# KIT_UNAZ.net
KiCad netlist of a schematic drawn in EAGLE
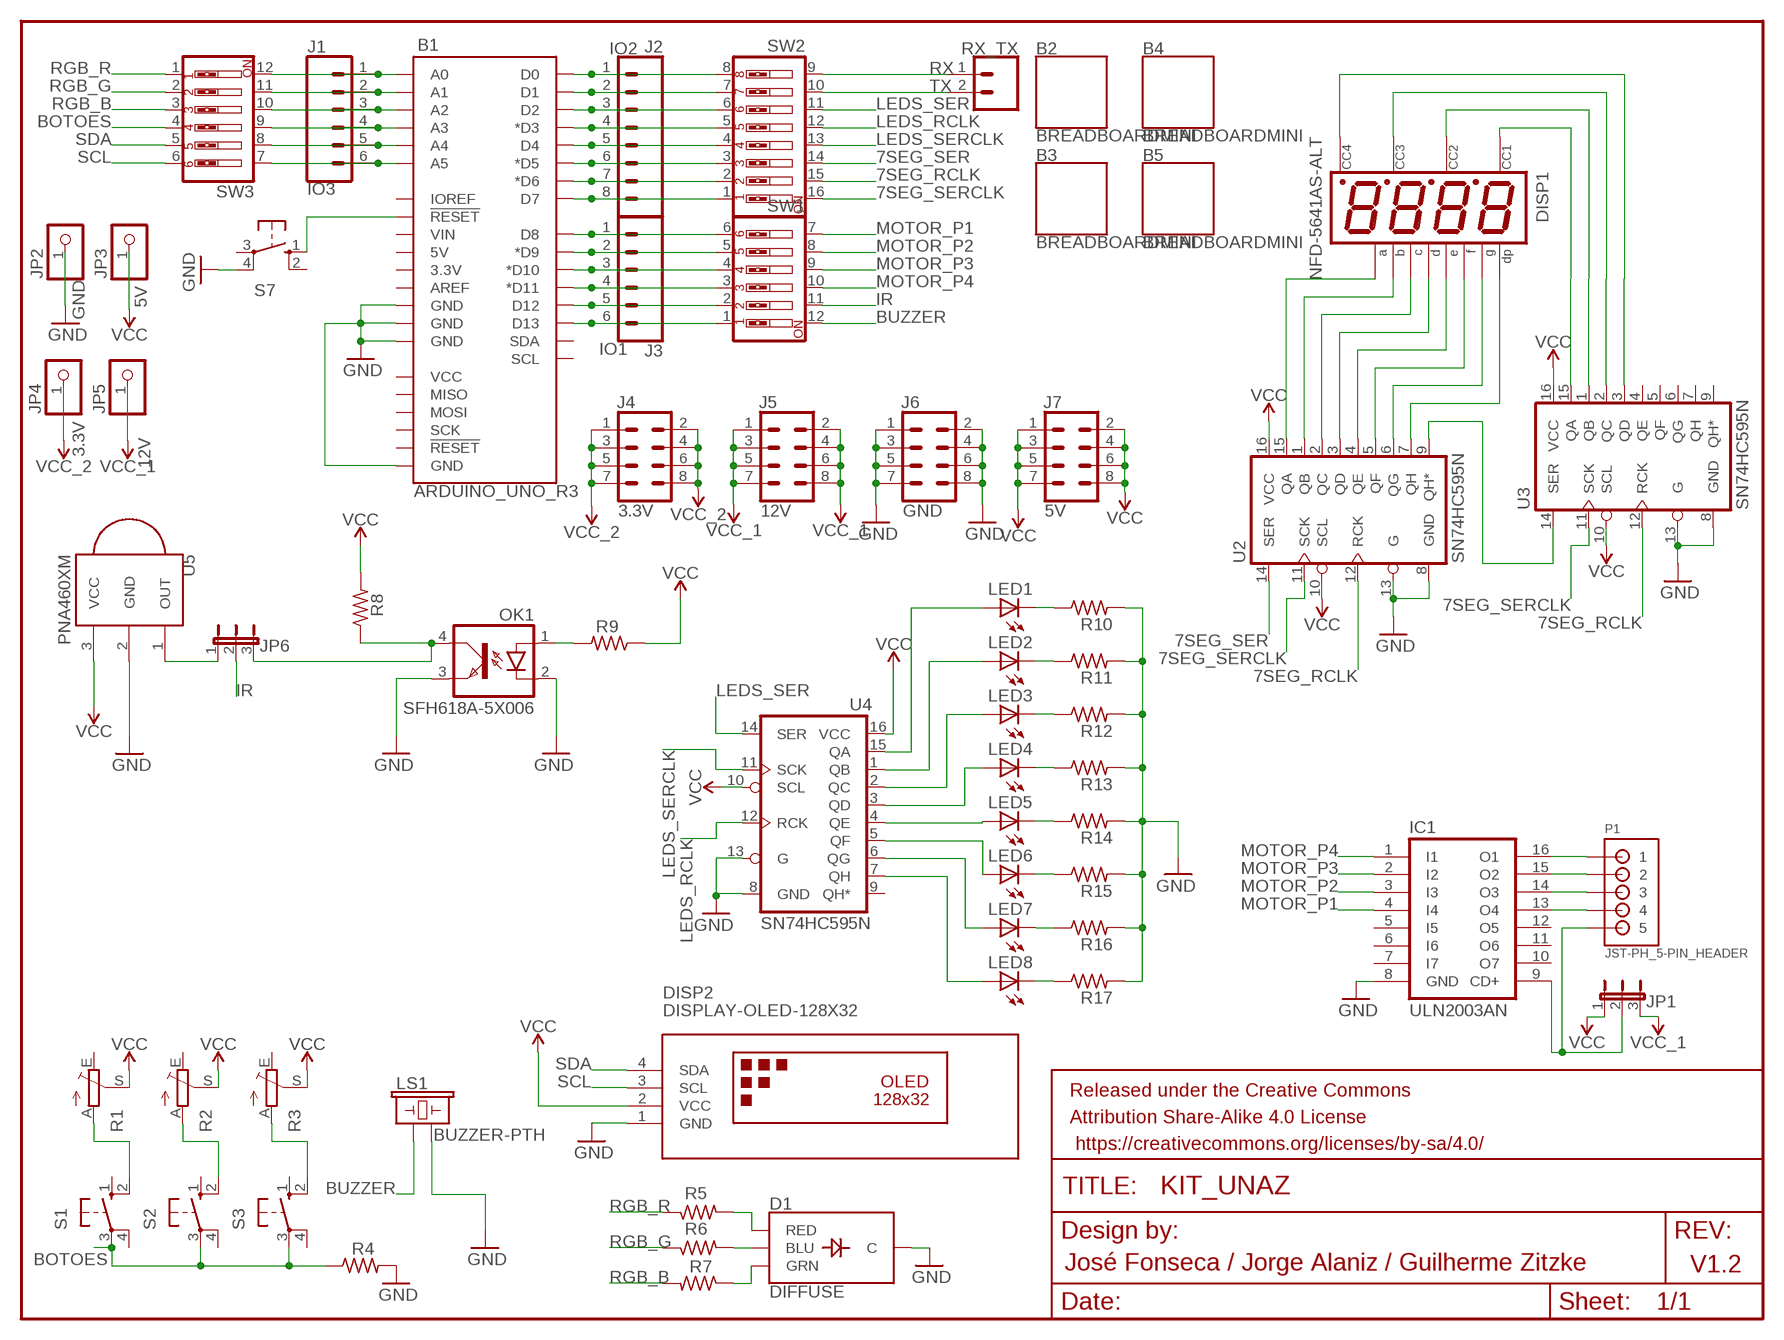
[diagram p0: schematic, sheet 1]

(export (version "E")
  (design (tool "Eeschema 10.0.6"))
  (components
    (comp (ref "B1")
      (value "ARDUINO_UNO_R3")
      (footprint "eagle-import:ARDUINO_R3")
      (libsource (lib "eagle-import") (part "ARDUINO_UNO_R3"))
    )
    (comp (ref "B2")
      (value "BREADBOARDMINI")
      (footprint "eagle-import:BREADBOARD-MINI")
      (libsource (lib "eagle-import") (part "BREADBOARDMINI"))
    )
    (comp (ref "B3")
      (value "BREADBOARDMINI")
      (footprint "eagle-import:BREADBOARD-MINI")
      (libsource (lib "eagle-import") (part "BREADBOARDMINI"))
    )
    (comp (ref "B4")
      (value "BREADBOARDMINI")
      (footprint "eagle-import:BREADBOARD-MINI")
      (libsource (lib "eagle-import") (part "BREADBOARDMINI"))
    )
    (comp (ref "B5")
      (value "BREADBOARDMINI")
      (footprint "eagle-import:BREADBOARD-MINI")
      (libsource (lib "eagle-import") (part "BREADBOARDMINI"))
    )
    (comp (ref "D1")
      (value "DIFFUSE")
      (footprint "eagle-import:WS2812B-PTH-KIT")
      (libsource (lib "eagle-import") (part "LED-RGB-CCDIFFUSE"))
    )
    (comp (ref "DISP1")
      (value "NFD-5641AS-ALT")
      (footprint "eagle-import:NFD-5641")
      (libsource (lib "eagle-import") (part "NFD-5641AS-ALT"))
    )
    (comp (ref "DISP2")
      (value "DISPLAY-OLED-128X32")
      (footprint "eagle-import:DISPLAY-OLED-128X32")
      (libsource (lib "eagle-import") (part "DISPLAY-OLED-128X32"))
    )
    (comp (ref "FRAME1")
      (value "FRAME-LETTER")
      (footprint "eagle-import:CREATIVE_COMMONS")
      (libsource (lib "eagle-import") (part "FRAME-LETTER"))
    )
    (comp (ref "IC1")
      (value "ULN2003AN")
      (footprint "eagle-import:DIL16")
      (libsource (lib "eagle-import") (part "ULN2003AN"))
    )
    (comp (ref "J1")
      (value "IO3")
      (footprint "eagle-import:1X06")
      (libsource (lib "eagle-import") (part "CONN_06SILK_FEMALE_PTH"))
    )
    (comp (ref "J2")
      (value "IO2")
      (footprint "eagle-import:1X08")
      (libsource (lib "eagle-import") (part "CONN_08{dblquote}"))
    )
    (comp (ref "J3")
      (value "IO1")
      (footprint "eagle-import:1X06")
      (libsource (lib "eagle-import") (part "CONN_06SILK_FEMALE_PTH"))
    )
    (comp (ref "J4")
      (value "3.3V")
      (footprint "eagle-import:2X4")
      (libsource (lib "eagle-import") (part "CONN_04X2"))
    )
    (comp (ref "J5")
      (value "12V")
      (footprint "eagle-import:2X4")
      (libsource (lib "eagle-import") (part "CONN_04X2"))
    )
    (comp (ref "J6")
      (value "GND")
      (footprint "eagle-import:2X4")
      (libsource (lib "eagle-import") (part "CONN_04X2"))
    )
    (comp (ref "J7")
      (value "5V")
      (footprint "eagle-import:2X4")
      (libsource (lib "eagle-import") (part "CONN_04X2"))
    )
    (comp (ref "JP1")
      (value "JP2E")
      (footprint "eagle-import:JP2")
      (libsource (lib "eagle-import") (part "JP2E"))
    )
    (comp (ref "JP2")
      (value "GND")
      (footprint "eagle-import:1X01")
      (libsource (lib "eagle-import") (part "PINHD-1X1"))
    )
    (comp (ref "JP3")
      (value "5V")
      (footprint "eagle-import:1X01")
      (libsource (lib "eagle-import") (part "PINHD-1X1"))
    )
    (comp (ref "JP4")
      (value "3.3V")
      (footprint "eagle-import:1X01")
      (libsource (lib "eagle-import") (part "PINHD-1X1"))
    )
    (comp (ref "JP5")
      (value "12V")
      (footprint "eagle-import:1X01")
      (libsource (lib "eagle-import") (part "PINHD-1X1"))
    )
    (comp (ref "JP6")
      (value "JP2E")
      (footprint "eagle-import:JP2")
      (libsource (lib "eagle-import") (part "JP2E"))
    )
    (comp (ref "LED1")
      (value "LED5MM")
      (footprint "eagle-import:LED5MM")
      (libsource (lib "eagle-import") (part "LED5MM"))
    )
    (comp (ref "LED2")
      (value "LED5MM")
      (footprint "eagle-import:LED5MM")
      (libsource (lib "eagle-import") (part "LED5MM"))
    )
    (comp (ref "LED3")
      (value "LED5MM")
      (footprint "eagle-import:LED5MM")
      (libsource (lib "eagle-import") (part "LED5MM"))
    )
    (comp (ref "LED4")
      (value "LED5MM")
      (footprint "eagle-import:LED5MM")
      (libsource (lib "eagle-import") (part "LED5MM"))
    )
    (comp (ref "LED5")
      (value "LED5MM")
      (footprint "eagle-import:LED5MM")
      (libsource (lib "eagle-import") (part "LED5MM"))
    )
    (comp (ref "LED6")
      (value "LED5MM")
      (footprint "eagle-import:LED5MM")
      (libsource (lib "eagle-import") (part "LED5MM"))
    )
    (comp (ref "LED7")
      (value "LED5MM")
      (footprint "eagle-import:LED5MM")
      (libsource (lib "eagle-import") (part "LED5MM"))
    )
    (comp (ref "LED8")
      (value "LED5MM")
      (footprint "eagle-import:LED5MM")
      (libsource (lib "eagle-import") (part "LED5MM"))
    )
    (comp (ref "LS1")
      (value "BUZZER-PTH")
      (footprint "eagle-import:BUZZER-12MM")
      (libsource (lib "eagle-import") (part "BUZZER-PTH"))
    )
    (comp (ref "OK1")
      (value "SFH618A-5X006")
      (footprint "eagle-import:DIP4-400")
      (libsource (lib "eagle-import") (part "SFH618?A-5X006"))
    )
    (comp (ref "P1")
      (value "JST-PH_5-PIN_HEADER")
      (footprint "eagle-import:JST_B5B-PH_HEADER")
      (libsource (lib "eagle-import") (part "JST-PH_5-PIN_HEADER"))
    )
    (comp (ref "R1")
      (value "TRIM_EU-B64Y")
      (footprint "eagle-import:B64Y")
      (libsource (lib "eagle-import") (part "TRIM_EU-B64Y"))
    )
    (comp (ref "R2")
      (value "TRIM_EU-B64Y")
      (footprint "eagle-import:B64Y")
      (libsource (lib "eagle-import") (part "TRIM_EU-B64Y"))
    )
    (comp (ref "R3")
      (value "TRIM_EU-B64Y")
      (footprint "eagle-import:B64Y")
      (libsource (lib "eagle-import") (part "TRIM_EU-B64Y"))
    )
    (comp (ref "R4")
      (value "R-US_0204/7")
      (footprint "eagle-import:0204_7")
      (libsource (lib "eagle-import") (part "R-US_0204/7"))
    )
    (comp (ref "R5")
      (value "R-US_0204/7")
      (footprint "eagle-import:0204_7")
      (libsource (lib "eagle-import") (part "R-US_0204/7"))
    )
    (comp (ref "R6")
      (value "R-US_0204/7")
      (footprint "eagle-import:0204_7")
      (libsource (lib "eagle-import") (part "R-US_0204/7"))
    )
    (comp (ref "R7")
      (value "R-US_0204/7")
      (footprint "eagle-import:0204_7")
      (libsource (lib "eagle-import") (part "R-US_0204/7"))
    )
    (comp (ref "R8")
      (value "R-US_0204/7")
      (footprint "eagle-import:0204_7")
      (libsource (lib "eagle-import") (part "R-US_0204/7"))
    )
    (comp (ref "R9")
      (value "R-US_0204/7")
      (footprint "eagle-import:0204_7")
      (libsource (lib "eagle-import") (part "R-US_0204/7"))
    )
    (comp (ref "R10")
      (value "R-US_0204/7")
      (footprint "eagle-import:0204_7")
      (libsource (lib "eagle-import") (part "R-US_0204/7"))
    )
    (comp (ref "R11")
      (value "R-US_0204/7")
      (footprint "eagle-import:0204_7")
      (libsource (lib "eagle-import") (part "R-US_0204/7"))
    )
    (comp (ref "R12")
      (value "R-US_0204/7")
      (footprint "eagle-import:0204_7")
      (libsource (lib "eagle-import") (part "R-US_0204/7"))
    )
    (comp (ref "R13")
      (value "R-US_0204/7")
      (footprint "eagle-import:0204_7")
      (libsource (lib "eagle-import") (part "R-US_0204/7"))
    )
    (comp (ref "R14")
      (value "R-US_0204/7")
      (footprint "eagle-import:0204_7")
      (libsource (lib "eagle-import") (part "R-US_0204/7"))
    )
    (comp (ref "R15")
      (value "R-US_0204/7")
      (footprint "eagle-import:0204_7")
      (libsource (lib "eagle-import") (part "R-US_0204/7"))
    )
    (comp (ref "R16")
      (value "R-US_0204/7")
      (footprint "eagle-import:0204_7")
      (libsource (lib "eagle-import") (part "R-US_0204/7"))
    )
    (comp (ref "R17")
      (value "R-US_0204/7")
      (footprint "eagle-import:0204_7")
      (libsource (lib "eagle-import") (part "R-US_0204/7"))
    )
    (comp (ref "RX_TX")
      (value "CONN_02")
      (footprint "eagle-import:1X02")
      (libsource (lib "eagle-import") (part "CONN_02"))
    )
    (comp (ref "S1")
      (value "40-XX")
      (footprint "eagle-import:B3F-40XX")
      (fields (field (name "MF") "OMRON COMPONENTS USA") (field (name "MPN") "B3F-4000"))
      (libsource (lib "eagle-import") (part "40-XX"))
    )
    (comp (ref "S2")
      (value "40-XX")
      (footprint "eagle-import:B3F-40XX")
      (fields (field (name "MF") "OMRON COMPONENTS USA") (field (name "MPN") "B3F-4000"))
      (libsource (lib "eagle-import") (part "40-XX"))
    )
    (comp (ref "S3")
      (value "40-XX")
      (footprint "eagle-import:B3F-40XX")
      (fields (field (name "MF") "OMRON COMPONENTS USA") (field (name "MPN") "B3F-4000"))
      (libsource (lib "eagle-import") (part "40-XX"))
    )
    (comp (ref "S7")
      (value "40-XX")
      (footprint "eagle-import:B3F-40XX")
      (fields (field (name "MF") "OMRON COMPONENTS USA") (field (name "MPN") "B3F-4000"))
      (libsource (lib "eagle-import") (part "40-XX"))
    )
    (comp (ref "SW1")
      (value "SW_DIP-6")
      (footprint "eagle-import:EDG-06")
      (libsource (lib "eagle-import") (part "SW_DIP-6"))
    )
    (comp (ref "SW2")
      (value "SW_DIP-8")
      (footprint "eagle-import:EDG-08")
      (libsource (lib "eagle-import") (part "SW_DIP-8"))
    )
    (comp (ref "SW3")
      (value "SW_DIP-6")
      (footprint "eagle-import:EDG-06")
      (libsource (lib "eagle-import") (part "SW_DIP-6"))
    )
    (comp (ref "U2")
      (value "SN74HC595N")
      (footprint "eagle-import:DIP16")
      (libsource (lib "eagle-import") (part "74595NHC"))
    )
    (comp (ref "U3")
      (value "SN74HC595N")
      (footprint "eagle-import:DIP16")
      (libsource (lib "eagle-import") (part "74595NHC"))
    )
    (comp (ref "U4")
      (value "SN74HC595N")
      (footprint "eagle-import:DIP16")
      (libsource (lib "eagle-import") (part "74595NHC"))
    )
    (comp (ref "U5")
      (value "PNA460XM")
      (footprint "eagle-import:PNA460XM")
      (libsource (lib "eagle-import") (part "PNA460XM"))
    )
  )
  (nets
    (net (code "1") (name "/7SEG_RCLK") (class "Default")
      (node (ref "SW2") (pin "15") (pinfunction "15_15") (pintype "passive"))
      (node (ref "U2") (pin "12") (pinfunction "RCK_12") (pintype "input"))
      (node (ref "U3") (pin "12") (pinfunction "RCK_12") (pintype "input"))
    )
    (net (code "2") (name "/7SEG_SER") (class "Default")
      (node (ref "SW2") (pin "14") (pinfunction "14_14") (pintype "passive"))
      (node (ref "U2") (pin "14") (pinfunction "SER_14") (pintype "input"))
    )
    (net (code "3") (name "/7SEG_SERCLK") (class "Default")
      (node (ref "SW2") (pin "16") (pinfunction "16_16") (pintype "passive"))
      (node (ref "U2") (pin "11") (pinfunction "SCK_11") (pintype "input"))
      (node (ref "U3") (pin "11") (pinfunction "SCK_11") (pintype "input"))
    )
    (net (code "4") (name "/BOTOES") (class "Default")
      (node (ref "R4") (pin "1") (pinfunction "1_1") (pintype "passive"))
      (node (ref "S1") (pin "3") (pinfunction "P_3") (pintype "passive"))
      (node (ref "S2") (pin "3") (pinfunction "P_3") (pintype "passive"))
      (node (ref "S3") (pin "3") (pinfunction "P_3") (pintype "passive"))
      (node (ref "SW3") (pin "4") (pinfunction "4_4") (pintype "passive"))
    )
    (net (code "5") (name "/BUZZER") (class "Default")
      (node (ref "LS1") (pin "+") (pinfunction "1_+") (pintype "passive"))
      (node (ref "SW1") (pin "12") (pinfunction "12_12") (pintype "passive"))
    )
    (net (code "6") (name "/IR") (class "Default")
      (node (ref "JP6") (pin "2") (pinfunction "2_2") (pintype "passive"))
      (node (ref "SW1") (pin "11") (pinfunction "11_11") (pintype "passive"))
    )
    (net (code "7") (name "/LEDS_RCLK") (class "Default")
      (node (ref "SW2") (pin "12") (pinfunction "12_12") (pintype "passive"))
      (node (ref "U4") (pin "12") (pinfunction "RCK_12") (pintype "input"))
    )
    (net (code "8") (name "/LEDS_SER") (class "Default")
      (node (ref "SW2") (pin "11") (pinfunction "11_11") (pintype "passive"))
      (node (ref "U4") (pin "14") (pinfunction "SER_14") (pintype "input"))
    )
    (net (code "9") (name "/LEDS_SERCLK") (class "Default")
      (node (ref "SW2") (pin "13") (pinfunction "13_13") (pintype "passive"))
      (node (ref "U4") (pin "11") (pinfunction "SCK_11") (pintype "input"))
    )
    (net (code "10") (name "/MOTOR_P1") (class "Default")
      (node (ref "IC1") (pin "4") (pinfunction "I4_4") (pintype "input"))
      (node (ref "SW1") (pin "7") (pinfunction "7_7") (pintype "passive"))
    )
    (net (code "11") (name "/MOTOR_P2") (class "Default")
      (node (ref "IC1") (pin "3") (pinfunction "I3_3") (pintype "input"))
      (node (ref "SW1") (pin "8") (pinfunction "8_8") (pintype "passive"))
    )
    (net (code "12") (name "/MOTOR_P3") (class "Default")
      (node (ref "IC1") (pin "2") (pinfunction "I2_2") (pintype "input"))
      (node (ref "SW1") (pin "9") (pinfunction "9_9") (pintype "passive"))
    )
    (net (code "13") (name "/MOTOR_P4") (class "Default")
      (node (ref "IC1") (pin "1") (pinfunction "I1_1") (pintype "input"))
      (node (ref "SW1") (pin "10") (pinfunction "10_10") (pintype "passive"))
    )
    (net (code "14") (name "/RGB_B") (class "Default")
      (node (ref "R7") (pin "2") (pinfunction "2_2") (pintype "passive"))
      (node (ref "SW3") (pin "2") (pinfunction "2_2") (pintype "passive"))
    )
    (net (code "15") (name "/RGB_G") (class "Default")
      (node (ref "R6") (pin "1") (pinfunction "1_1") (pintype "passive"))
      (node (ref "SW3") (pin "3") (pinfunction "3_3") (pintype "passive"))
    )
    (net (code "16") (name "/RGB_R") (class "Default")
      (node (ref "R5") (pin "1") (pinfunction "1_1") (pintype "passive"))
      (node (ref "SW3") (pin "1") (pinfunction "1_1") (pintype "passive"))
    )
    (net (code "17") (name "/RX") (class "Default")
      (node (ref "RX_TX") (pin "1") (pinfunction "1_1") (pintype "passive"))
      (node (ref "SW2") (pin "9") (pinfunction "9_9") (pintype "passive"))
    )
    (net (code "18") (name "/SCL") (class "Default")
      (node (ref "DISP2") (pin "3") (pinfunction "SCL_3") (pintype "bidirectional"))
      (node (ref "SW3") (pin "6") (pinfunction "6_6") (pintype "passive"))
    )
    (net (code "19") (name "/SDA") (class "Default")
      (node (ref "DISP2") (pin "4") (pinfunction "SDA_4") (pintype "bidirectional"))
      (node (ref "SW3") (pin "5") (pinfunction "5_5") (pintype "passive"))
    )
    (net (code "20") (name "/TX") (class "Default")
      (node (ref "RX_TX") (pin "2") (pinfunction "2_2") (pintype "passive"))
      (node (ref "SW2") (pin "10") (pinfunction "10_10") (pintype "passive"))
    )
    (net (code "21") (name "GND") (class "Default")
      (node (ref "B1") (pin "GND@1") (pinfunction "GND_GND@1") (pintype "bidirectional"))
      (node (ref "B1") (pin "GND@2") (pinfunction "GND_GND@2") (pintype "bidirectional"))
      (node (ref "B1") (pin "GND@3") (pinfunction "GND_GND@3") (pintype "bidirectional"))
      (node (ref "B1") (pin "GND@4") (pinfunction "GND_GND@4") (pintype "bidirectional"))
      (node (ref "D1") (pin "2") (pinfunction "C_2") (pintype "bidirectional"))
      (node (ref "DISP2") (pin "1") (pinfunction "GND_1") (pintype "power_in"))
      (node (ref "IC1") (pin "8") (pinfunction "GND_8") (pintype "power_in"))
      (node (ref "J6") (pin "1") (pinfunction "1_1") (pintype "passive"))
      (node (ref "J6") (pin "2") (pinfunction "2_2") (pintype "passive"))
      (node (ref "J6") (pin "3") (pinfunction "3_3") (pintype "passive"))
      (node (ref "J6") (pin "4") (pinfunction "4_4") (pintype "passive"))
      (node (ref "J6") (pin "5") (pinfunction "5_5") (pintype "passive"))
      (node (ref "J6") (pin "6") (pinfunction "6_6") (pintype "passive"))
      (node (ref "J6") (pin "7") (pinfunction "7_7") (pintype "passive"))
      (node (ref "J6") (pin "8") (pinfunction "8_8") (pintype "passive"))
      (node (ref "JP2") (pin "1") (pinfunction "1_1") (pintype "passive"))
      (node (ref "LS1") (pin "-") (pinfunction "2_-") (pintype "passive"))
      (node (ref "OK1") (pin "2") (pinfunction "C_2") (pintype "passive"))
      (node (ref "OK1") (pin "3") (pinfunction "EMIT_3") (pintype "passive"))
      (node (ref "R10") (pin "2") (pinfunction "2_2") (pintype "passive"))
      (node (ref "R11") (pin "2") (pinfunction "2_2") (pintype "passive"))
      (node (ref "R12") (pin "2") (pinfunction "2_2") (pintype "passive"))
      (node (ref "R13") (pin "2") (pinfunction "2_2") (pintype "passive"))
      (node (ref "R14") (pin "2") (pinfunction "2_2") (pintype "passive"))
      (node (ref "R15") (pin "2") (pinfunction "2_2") (pintype "passive"))
      (node (ref "R16") (pin "2") (pinfunction "2_2") (pintype "passive"))
      (node (ref "R17") (pin "2") (pinfunction "2_2") (pintype "passive"))
      (node (ref "R4") (pin "2") (pinfunction "2_2") (pintype "passive"))
      (node (ref "S7") (pin "4") (pinfunction "P1_4") (pintype "passive"))
      (node (ref "U2") (pin "13") (pinfunction "G_13") (pintype "input"))
      (node (ref "U2") (pin "8") (pinfunction "GND_8") (pintype "power_in"))
      (node (ref "U3") (pin "13") (pinfunction "G_13") (pintype "input"))
      (node (ref "U3") (pin "8") (pinfunction "GND_8") (pintype "power_in"))
      (node (ref "U4") (pin "13") (pinfunction "G_13") (pintype "input"))
      (node (ref "U4") (pin "8") (pinfunction "GND_8") (pintype "power_in"))
      (node (ref "U5") (pin "2") (pinfunction "GND_2") (pintype "power_in"))
    )
    (net (code "22") (name "Net-(B1-*D3)") (class "Default")
      (node (ref "B1") (pin "D3") (pinfunction "*D3_D3") (pintype "bidirectional"))
      (node (ref "J2") (pin "4") (pinfunction "4_4") (pintype "passive"))
      (node (ref "SW2") (pin "5") (pinfunction "5_5") (pintype "passive"))
    )
    (net (code "23") (name "Net-(B1-*D5)") (class "Default")
      (node (ref "B1") (pin "D5") (pinfunction "*D5_D5") (pintype "bidirectional"))
      (node (ref "J2") (pin "6") (pinfunction "6_6") (pintype "passive"))
      (node (ref "SW2") (pin "3") (pinfunction "3_3") (pintype "passive"))
    )
    (net (code "24") (name "Net-(B1-*D6)") (class "Default")
      (node (ref "B1") (pin "D6") (pinfunction "*D6_D6") (pintype "bidirectional"))
      (node (ref "J2") (pin "7") (pinfunction "7_7") (pintype "passive"))
      (node (ref "SW2") (pin "2") (pinfunction "2_2") (pintype "passive"))
    )
    (net (code "25") (name "Net-(B1-*D9)") (class "Default")
      (node (ref "B1") (pin "D9") (pinfunction "*D9_D9") (pintype "bidirectional"))
      (node (ref "J3") (pin "2") (pinfunction "2_2") (pintype "passive"))
      (node (ref "SW1") (pin "5") (pinfunction "5_5") (pintype "passive"))
    )
    (net (code "26") (name "Net-(B1-*D10)") (class "Default")
      (node (ref "B1") (pin "D10") (pinfunction "*D10_D10") (pintype "bidirectional"))
      (node (ref "J3") (pin "3") (pinfunction "3_3") (pintype "passive"))
      (node (ref "SW1") (pin "4") (pinfunction "4_4") (pintype "passive"))
    )
    (net (code "27") (name "Net-(B1-*D11)") (class "Default")
      (node (ref "B1") (pin "D11") (pinfunction "*D11_D11") (pintype "bidirectional"))
      (node (ref "J3") (pin "4") (pinfunction "4_4") (pintype "passive"))
      (node (ref "SW1") (pin "3") (pinfunction "3_3") (pintype "passive"))
    )
    (net (code "28") (name "Net-(B1-PadA0)") (class "Default")
      (node (ref "B1") (pin "A0") (pinfunction "A0_A0") (pintype "bidirectional"))
      (node (ref "J1") (pin "1") (pinfunction "1_1") (pintype "passive"))
      (node (ref "SW3") (pin "12") (pinfunction "12_12") (pintype "passive"))
    )
    (net (code "29") (name "Net-(B1-PadA1)") (class "Default")
      (node (ref "B1") (pin "A1") (pinfunction "A1_A1") (pintype "bidirectional"))
      (node (ref "J1") (pin "2") (pinfunction "2_2") (pintype "passive"))
      (node (ref "SW3") (pin "11") (pinfunction "11_11") (pintype "passive"))
    )
    (net (code "30") (name "Net-(B1-PadA2)") (class "Default")
      (node (ref "B1") (pin "A2") (pinfunction "A2_A2") (pintype "bidirectional"))
      (node (ref "J1") (pin "3") (pinfunction "3_3") (pintype "passive"))
      (node (ref "SW3") (pin "10") (pinfunction "10_10") (pintype "passive"))
    )
    (net (code "31") (name "Net-(B1-PadA3)") (class "Default")
      (node (ref "B1") (pin "A3") (pinfunction "A3_A3") (pintype "bidirectional"))
      (node (ref "J1") (pin "4") (pinfunction "4_4") (pintype "passive"))
      (node (ref "SW3") (pin "9") (pinfunction "9_9") (pintype "passive"))
    )
    (net (code "32") (name "Net-(B1-PadA4)") (class "Default")
      (node (ref "B1") (pin "A4") (pinfunction "A4_A4") (pintype "bidirectional"))
      (node (ref "J1") (pin "5") (pinfunction "5_5") (pintype "passive"))
      (node (ref "SW3") (pin "8") (pinfunction "8_8") (pintype "passive"))
    )
    (net (code "33") (name "Net-(B1-PadA5)") (class "Default")
      (node (ref "B1") (pin "A5") (pinfunction "A5_A5") (pintype "bidirectional"))
      (node (ref "J1") (pin "6") (pinfunction "6_6") (pintype "passive"))
      (node (ref "SW3") (pin "7") (pinfunction "7_7") (pintype "passive"))
    )
    (net (code "34") (name "Net-(B1-PadD0)") (class "Default")
      (node (ref "B1") (pin "D0") (pinfunction "D0_D0") (pintype "bidirectional"))
      (node (ref "J2") (pin "1") (pinfunction "1_1") (pintype "passive"))
      (node (ref "SW2") (pin "8") (pinfunction "8_8") (pintype "passive"))
    )
    (net (code "35") (name "Net-(B1-PadD1)") (class "Default")
      (node (ref "B1") (pin "D1") (pinfunction "D1_D1") (pintype "bidirectional"))
      (node (ref "J2") (pin "2") (pinfunction "2_2") (pintype "passive"))
      (node (ref "SW2") (pin "7") (pinfunction "7_7") (pintype "passive"))
    )
    (net (code "36") (name "Net-(B1-PadD2)") (class "Default")
      (node (ref "B1") (pin "D2") (pinfunction "D2_D2") (pintype "bidirectional"))
      (node (ref "J2") (pin "3") (pinfunction "3_3") (pintype "passive"))
      (node (ref "SW2") (pin "6") (pinfunction "6_6") (pintype "passive"))
    )
    (net (code "37") (name "Net-(B1-PadD4)") (class "Default")
      (node (ref "B1") (pin "D4") (pinfunction "D4_D4") (pintype "bidirectional"))
      (node (ref "J2") (pin "5") (pinfunction "5_5") (pintype "passive"))
      (node (ref "SW2") (pin "4") (pinfunction "4_4") (pintype "passive"))
    )
    (net (code "38") (name "Net-(B1-PadD7)") (class "Default")
      (node (ref "B1") (pin "D7") (pinfunction "D7_D7") (pintype "bidirectional"))
      (node (ref "J2") (pin "8") (pinfunction "8_8") (pintype "passive"))
      (node (ref "SW2") (pin "1") (pinfunction "1_1") (pintype "passive"))
    )
    (net (code "39") (name "Net-(B1-PadD8)") (class "Default")
      (node (ref "B1") (pin "D8") (pinfunction "D8_D8") (pintype "bidirectional"))
      (node (ref "J3") (pin "1") (pinfunction "1_1") (pintype "passive"))
      (node (ref "SW1") (pin "6") (pinfunction "6_6") (pintype "passive"))
    )
    (net (code "40") (name "Net-(B1-PadD12)") (class "Default")
      (node (ref "B1") (pin "D12") (pinfunction "D12_D12") (pintype "bidirectional"))
      (node (ref "J3") (pin "5") (pinfunction "5_5") (pintype "passive"))
      (node (ref "SW1") (pin "2") (pinfunction "2_2") (pintype "passive"))
    )
    (net (code "41") (name "Net-(B1-PadD13)") (class "Default")
      (node (ref "B1") (pin "D13") (pinfunction "D13_D13") (pintype "bidirectional"))
      (node (ref "J3") (pin "6") (pinfunction "6_6") (pintype "passive"))
      (node (ref "SW1") (pin "1") (pinfunction "1_1") (pintype "passive"))
    )
    (net (code "42") (name "Net-(D1-BLU)") (class "Default")
      (node (ref "D1") (pin "4") (pinfunction "BLU_4") (pintype "bidirectional"))
      (node (ref "R6") (pin "2") (pinfunction "2_2") (pintype "passive"))
    )
    (net (code "43") (name "Net-(D1-GRN)") (class "Default")
      (node (ref "D1") (pin "3") (pinfunction "GRN_3") (pintype "bidirectional"))
      (node (ref "R7") (pin "1") (pinfunction "1_1") (pintype "passive"))
    )
    (net (code "44") (name "Net-(D1-RED)") (class "Default")
      (node (ref "D1") (pin "1") (pinfunction "RED_1") (pintype "bidirectional"))
      (node (ref "R5") (pin "2") (pinfunction "2_2") (pintype "passive"))
    )
    (net (code "45") (name "Net-(IC1-CD+)") (class "Default")
      (node (ref "IC1") (pin "9") (pinfunction "CD+_9") (pintype "passive"))
      (node (ref "JP1") (pin "2") (pinfunction "2_2") (pintype "passive"))
      (node (ref "P1") (pin "P5") (pinfunction "5_P5") (pintype "bidirectional"))
    )
    (net (code "46") (name "Net-(IC1-O1)") (class "Default")
      (node (ref "IC1") (pin "16") (pinfunction "O1_16") (pintype "open_collector"))
      (node (ref "P1") (pin "P1") (pinfunction "1_P1") (pintype "bidirectional"))
    )
    (net (code "47") (name "Net-(IC1-O2)") (class "Default")
      (node (ref "IC1") (pin "15") (pinfunction "O2_15") (pintype "open_collector"))
      (node (ref "P1") (pin "P2") (pinfunction "2_P2") (pintype "bidirectional"))
    )
    (net (code "48") (name "Net-(IC1-O3)") (class "Default")
      (node (ref "IC1") (pin "14") (pinfunction "O3_14") (pintype "open_collector"))
      (node (ref "P1") (pin "P3") (pinfunction "3_P3") (pintype "bidirectional"))
    )
    (net (code "49") (name "Net-(IC1-O4)") (class "Default")
      (node (ref "IC1") (pin "13") (pinfunction "O4_13") (pintype "open_collector"))
      (node (ref "P1") (pin "P4") (pinfunction "4_P4") (pintype "bidirectional"))
    )
    (net (code "50") (name "Net-(LED1-C)") (class "Default")
      (node (ref "LED1") (pin "K") (pinfunction "C_K") (pintype "passive"))
      (node (ref "R10") (pin "1") (pinfunction "1_1") (pintype "passive"))
    )
    (net (code "51") (name "Net-(LED2-C)") (class "Default")
      (node (ref "LED2") (pin "K") (pinfunction "C_K") (pintype "passive"))
      (node (ref "R11") (pin "1") (pinfunction "1_1") (pintype "passive"))
    )
    (net (code "52") (name "Net-(LED3-C)") (class "Default")
      (node (ref "LED3") (pin "K") (pinfunction "C_K") (pintype "passive"))
      (node (ref "R12") (pin "1") (pinfunction "1_1") (pintype "passive"))
    )
    (net (code "53") (name "Net-(LED4-C)") (class "Default")
      (node (ref "LED4") (pin "K") (pinfunction "C_K") (pintype "passive"))
      (node (ref "R13") (pin "1") (pinfunction "1_1") (pintype "passive"))
    )
    (net (code "54") (name "Net-(LED5-C)") (class "Default")
      (node (ref "LED5") (pin "K") (pinfunction "C_K") (pintype "passive"))
      (node (ref "R14") (pin "1") (pinfunction "1_1") (pintype "passive"))
    )
    (net (code "55") (name "Net-(LED6-C)") (class "Default")
      (node (ref "LED6") (pin "K") (pinfunction "C_K") (pintype "passive"))
      (node (ref "R15") (pin "1") (pinfunction "1_1") (pintype "passive"))
    )
    (net (code "56") (name "Net-(LED7-C)") (class "Default")
      (node (ref "LED7") (pin "K") (pinfunction "C_K") (pintype "passive"))
      (node (ref "R16") (pin "1") (pinfunction "1_1") (pintype "passive"))
    )
    (net (code "57") (name "Net-(LED8-C)") (class "Default")
      (node (ref "LED8") (pin "K") (pinfunction "C_K") (pintype "passive"))
      (node (ref "R17") (pin "1") (pinfunction "1_1") (pintype "passive"))
    )
    (net (code "58") (name "Net-(OK1-A)") (class "Default")
      (node (ref "OK1") (pin "1") (pinfunction "A_1") (pintype "passive"))
      (node (ref "R9") (pin "2") (pinfunction "2_2") (pintype "passive"))
    )
    (net (code "59") (name "Net-(OK1-COL)") (class "Default")
      (node (ref "JP6") (pin "3") (pinfunction "3_3") (pintype "passive"))
      (node (ref "OK1") (pin "4") (pinfunction "COL_4") (pintype "passive"))
      (node (ref "R8") (pin "1") (pinfunction "1_1") (pintype "passive"))
    )
    (net (code "60") (name "Net-(S1-S1)") (class "Default")
      (node (ref "R1") (pin "A") (pinfunction "A_A") (pintype "passive"))
      (node (ref "S1") (pin "2") (pinfunction "S1_2") (pintype "passive"))
    )
    (net (code "61") (name "Net-(S2-S1)") (class "Default")
      (node (ref "R2") (pin "A") (pinfunction "A_A") (pintype "passive"))
      (node (ref "S2") (pin "2") (pinfunction "S1_2") (pintype "passive"))
    )
    (net (code "62") (name "Net-(S3-S1)") (class "Default")
      (node (ref "R3") (pin "A") (pinfunction "A_A") (pintype "passive"))
      (node (ref "S3") (pin "2") (pinfunction "S1_2") (pintype "passive"))
    )
    (net (code "63") (name "Net-(S7-S)") (class "Default")
      (node (ref "B1") (pin "RESET@1") (pinfunction "~{RESET}_RESET@1") (pintype "bidirectional"))
      (node (ref "S7") (pin "1") (pinfunction "S_1") (pintype "passive"))
    )
    (net (code "64") (name "Net-(U2-QA)") (class "Default")
      (node (ref "DISP1") (pin "P$11") (pinfunction "P$11_P$11") (pintype "bidirectional"))
      (node (ref "U2") (pin "15") (pinfunction "QA_15") (pintype "tri_state"))
    )
    (net (code "65") (name "Net-(U2-QB)") (class "Default")
      (node (ref "DISP1") (pin "P$7") (pinfunction "P$7_P$7") (pintype "bidirectional"))
      (node (ref "U2") (pin "1") (pinfunction "QB_1") (pintype "tri_state"))
    )
    (net (code "66") (name "Net-(U2-QC)") (class "Default")
      (node (ref "DISP1") (pin "P$4") (pinfunction "P$4_P$4") (pintype "bidirectional"))
      (node (ref "U2") (pin "2") (pinfunction "QC_2") (pintype "tri_state"))
    )
    (net (code "67") (name "Net-(U2-QD)") (class "Default")
      (node (ref "DISP1") (pin "P$2") (pinfunction "P$2_P$2") (pintype "bidirectional"))
      (node (ref "U2") (pin "3") (pinfunction "QD_3") (pintype "tri_state"))
    )
    (net (code "68") (name "Net-(U2-QE)") (class "Default")
      (node (ref "DISP1") (pin "P$1") (pinfunction "P$1_P$1") (pintype "bidirectional"))
      (node (ref "U2") (pin "4") (pinfunction "QE_4") (pintype "tri_state"))
    )
    (net (code "69") (name "Net-(U2-QF)") (class "Default")
      (node (ref "DISP1") (pin "P$10") (pinfunction "P$10_P$10") (pintype "bidirectional"))
      (node (ref "U2") (pin "5") (pinfunction "QF_5") (pintype "tri_state"))
    )
    (net (code "70") (name "Net-(U2-QG)") (class "Default")
      (node (ref "DISP1") (pin "P$5") (pinfunction "P$5_P$5") (pintype "bidirectional"))
      (node (ref "U2") (pin "6") (pinfunction "QG_6") (pintype "tri_state"))
    )
    (net (code "71") (name "Net-(U2-QH)") (class "Default")
      (node (ref "DISP1") (pin "P$3") (pinfunction "P$3_P$3") (pintype "bidirectional"))
      (node (ref "U2") (pin "7") (pinfunction "QH_7") (pintype "tri_state"))
    )
    (net (code "72") (name "Net-(U2-QH*)") (class "Default")
      (node (ref "U2") (pin "9") (pinfunction "QH*_9") (pintype "tri_state"))
      (node (ref "U3") (pin "14") (pinfunction "SER_14") (pintype "input"))
    )
    (net (code "73") (name "Net-(U3-QA)") (class "Default")
      (node (ref "DISP1") (pin "P$12") (pinfunction "P$12_P$12") (pintype "bidirectional"))
      (node (ref "U3") (pin "15") (pinfunction "QA_15") (pintype "tri_state"))
    )
    (net (code "74") (name "Net-(U3-QB)") (class "Default")
      (node (ref "DISP1") (pin "P$9") (pinfunction "P$9_P$9") (pintype "bidirectional"))
      (node (ref "U3") (pin "1") (pinfunction "QB_1") (pintype "tri_state"))
    )
    (net (code "75") (name "Net-(U3-QC)") (class "Default")
      (node (ref "DISP1") (pin "P$8") (pinfunction "P$8_P$8") (pintype "bidirectional"))
      (node (ref "U3") (pin "2") (pinfunction "QC_2") (pintype "tri_state"))
    )
    (net (code "76") (name "Net-(U3-QD)") (class "Default")
      (node (ref "DISP1") (pin "P$6") (pinfunction "P$6_P$6") (pintype "bidirectional"))
      (node (ref "U3") (pin "3") (pinfunction "QD_3") (pintype "tri_state"))
    )
    (net (code "77") (name "Net-(U4-QA)") (class "Default")
      (node (ref "LED1") (pin "A") (pinfunction "A_A") (pintype "passive"))
      (node (ref "U4") (pin "15") (pinfunction "QA_15") (pintype "tri_state"))
    )
    (net (code "78") (name "Net-(U4-QB)") (class "Default")
      (node (ref "LED2") (pin "A") (pinfunction "A_A") (pintype "passive"))
      (node (ref "U4") (pin "1") (pinfunction "QB_1") (pintype "tri_state"))
    )
    (net (code "79") (name "Net-(U4-QC)") (class "Default")
      (node (ref "LED3") (pin "A") (pinfunction "A_A") (pintype "passive"))
      (node (ref "U4") (pin "2") (pinfunction "QC_2") (pintype "tri_state"))
    )
    (net (code "80") (name "Net-(U4-QD)") (class "Default")
      (node (ref "LED4") (pin "A") (pinfunction "A_A") (pintype "passive"))
      (node (ref "U4") (pin "3") (pinfunction "QD_3") (pintype "tri_state"))
    )
    (net (code "81") (name "Net-(U4-QE)") (class "Default")
      (node (ref "LED5") (pin "A") (pinfunction "A_A") (pintype "passive"))
      (node (ref "U4") (pin "4") (pinfunction "QE_4") (pintype "tri_state"))
    )
    (net (code "82") (name "Net-(U4-QF)") (class "Default")
      (node (ref "LED6") (pin "A") (pinfunction "A_A") (pintype "passive"))
      (node (ref "U4") (pin "5") (pinfunction "QF_5") (pintype "tri_state"))
    )
    (net (code "83") (name "Net-(U4-QG)") (class "Default")
      (node (ref "LED7") (pin "A") (pinfunction "A_A") (pintype "passive"))
      (node (ref "U4") (pin "6") (pinfunction "QG_6") (pintype "tri_state"))
    )
    (net (code "84") (name "Net-(U4-QH)") (class "Default")
      (node (ref "LED8") (pin "A") (pinfunction "A_A") (pintype "passive"))
      (node (ref "U4") (pin "7") (pinfunction "QH_7") (pintype "tri_state"))
    )
    (net (code "85") (name "Net-(U5-OUT)") (class "Default")
      (node (ref "JP6") (pin "1") (pinfunction "1_1") (pintype "passive"))
      (node (ref "U5") (pin "1") (pinfunction "OUT_1") (pintype "output"))
    )
    (net (code "86") (name "VCC") (class "Default")
      (node (ref "DISP2") (pin "2") (pinfunction "VCC_2") (pintype "power_in"))
      (node (ref "J7") (pin "1") (pinfunction "1_1") (pintype "passive"))
      (node (ref "J7") (pin "2") (pinfunction "2_2") (pintype "passive"))
      (node (ref "J7") (pin "3") (pinfunction "3_3") (pintype "passive"))
      (node (ref "J7") (pin "4") (pinfunction "4_4") (pintype "passive"))
      (node (ref "J7") (pin "5") (pinfunction "5_5") (pintype "passive"))
      (node (ref "J7") (pin "6") (pinfunction "6_6") (pintype "passive"))
      (node (ref "J7") (pin "7") (pinfunction "7_7") (pintype "passive"))
      (node (ref "J7") (pin "8") (pinfunction "8_8") (pintype "passive"))
      (node (ref "JP1") (pin "1") (pinfunction "1_1") (pintype "passive"))
      (node (ref "JP3") (pin "1") (pinfunction "1_1") (pintype "passive"))
      (node (ref "R1") (pin "S") (pinfunction "S_S") (pintype "passive"))
      (node (ref "R2") (pin "S") (pinfunction "S_S") (pintype "passive"))
      (node (ref "R3") (pin "S") (pinfunction "S_S") (pintype "passive"))
      (node (ref "R8") (pin "2") (pinfunction "2_2") (pintype "passive"))
      (node (ref "R9") (pin "1") (pinfunction "1_1") (pintype "passive"))
      (node (ref "U2") (pin "10") (pinfunction "SCL_10") (pintype "input"))
      (node (ref "U2") (pin "16") (pinfunction "VCC_16") (pintype "power_in"))
      (node (ref "U3") (pin "10") (pinfunction "SCL_10") (pintype "input"))
      (node (ref "U3") (pin "16") (pinfunction "VCC_16") (pintype "power_in"))
      (node (ref "U4") (pin "10") (pinfunction "SCL_10") (pintype "input"))
      (node (ref "U4") (pin "16") (pinfunction "VCC_16") (pintype "power_in"))
      (node (ref "U5") (pin "3") (pinfunction "VCC_3") (pintype "power_in"))
    )
    (net (code "87") (name "VCC_1") (class "Default")
      (node (ref "J5") (pin "1") (pinfunction "1_1") (pintype "passive"))
      (node (ref "J5") (pin "2") (pinfunction "2_2") (pintype "passive"))
      (node (ref "J5") (pin "3") (pinfunction "3_3") (pintype "passive"))
      (node (ref "J5") (pin "4") (pinfunction "4_4") (pintype "passive"))
      (node (ref "J5") (pin "5") (pinfunction "5_5") (pintype "passive"))
      (node (ref "J5") (pin "6") (pinfunction "6_6") (pintype "passive"))
      (node (ref "J5") (pin "7") (pinfunction "7_7") (pintype "passive"))
      (node (ref "J5") (pin "8") (pinfunction "8_8") (pintype "passive"))
      (node (ref "JP1") (pin "3") (pinfunction "3_3") (pintype "passive"))
      (node (ref "JP5") (pin "1") (pinfunction "1_1") (pintype "passive"))
    )
    (net (code "88") (name "VCC_2") (class "Default")
      (node (ref "J4") (pin "1") (pinfunction "1_1") (pintype "passive"))
      (node (ref "J4") (pin "2") (pinfunction "2_2") (pintype "passive"))
      (node (ref "J4") (pin "3") (pinfunction "3_3") (pintype "passive"))
      (node (ref "J4") (pin "4") (pinfunction "4_4") (pintype "passive"))
      (node (ref "J4") (pin "5") (pinfunction "5_5") (pintype "passive"))
      (node (ref "J4") (pin "6") (pinfunction "6_6") (pintype "passive"))
      (node (ref "J4") (pin "7") (pinfunction "7_7") (pintype "passive"))
      (node (ref "J4") (pin "8") (pinfunction "8_8") (pintype "passive"))
      (node (ref "JP4") (pin "1") (pinfunction "1_1") (pintype "passive"))
    )
    (net (code "89") (name "unconnected-(B1-Pad3.3V)") (class "Default")
      (node (ref "B1") (pin "3.3V") (pinfunction "3.3V_3.3V") (pintype "bidirectional"))
    )
    (net (code "90") (name "unconnected-(B1-Pad5V)") (class "Default")
      (node (ref "B1") (pin "5V") (pinfunction "5V_5V") (pintype "bidirectional"))
    )
    (net (code "91") (name "unconnected-(B1-PadAREF)") (class "Default")
      (node (ref "B1") (pin "AREF") (pinfunction "AREF_AREF") (pintype "bidirectional"))
    )
    (net (code "92") (name "unconnected-(B1-PadIOREF)") (class "Default")
      (node (ref "B1") (pin "IOREF") (pinfunction "IOREF_IOREF") (pintype "bidirectional"))
    )
    (net (code "93") (name "unconnected-(B1-PadMISO)") (class "Default")
      (node (ref "B1") (pin "MISO") (pinfunction "MISO_MISO") (pintype "bidirectional"))
    )
    (net (code "94") (name "unconnected-(B1-PadMOSI)") (class "Default")
      (node (ref "B1") (pin "MOSI") (pinfunction "MOSI_MOSI") (pintype "bidirectional"))
    )
    (net (code "95") (name "unconnected-(B1-PadSCK)") (class "Default")
      (node (ref "B1") (pin "SCK") (pinfunction "SCK_SCK") (pintype "bidirectional"))
    )
    (net (code "96") (name "unconnected-(B1-PadSCL)") (class "Default")
      (node (ref "B1") (pin "SCL") (pinfunction "SCL_SCL") (pintype "bidirectional"))
    )
    (net (code "97") (name "unconnected-(B1-PadSDA)") (class "Default")
      (node (ref "B1") (pin "SDA") (pinfunction "SDA_SDA") (pintype "bidirectional"))
    )
    (net (code "98") (name "unconnected-(B1-PadVCC)") (class "Default")
      (node (ref "B1") (pin "VCC") (pinfunction "VCC_VCC") (pintype "bidirectional"))
    )
    (net (code "99") (name "unconnected-(B1-PadVIN)") (class "Default")
      (node (ref "B1") (pin "VIN") (pinfunction "VIN_VIN") (pintype "bidirectional"))
    )
    (net (code "100") (name "unconnected-(B1-~{RESET}-PadRESET@2)") (class "Default")
      (node (ref "B1") (pin "RESET@2") (pinfunction "~{RESET}_RESET@2") (pintype "bidirectional"))
    )
    (net (code "101") (name "unconnected-(IC1-I5-Pad5)") (class "Default")
      (node (ref "IC1") (pin "5") (pinfunction "I5_5") (pintype "input"))
    )
    (net (code "102") (name "unconnected-(IC1-I6-Pad6)") (class "Default")
      (node (ref "IC1") (pin "6") (pinfunction "I6_6") (pintype "input"))
    )
    (net (code "103") (name "unconnected-(IC1-I7-Pad7)") (class "Default")
      (node (ref "IC1") (pin "7") (pinfunction "I7_7") (pintype "input"))
    )
    (net (code "104") (name "unconnected-(IC1-O5-Pad12)") (class "Default")
      (node (ref "IC1") (pin "12") (pinfunction "O5_12") (pintype "open_collector"))
    )
    (net (code "105") (name "unconnected-(IC1-O6-Pad11)") (class "Default")
      (node (ref "IC1") (pin "11") (pinfunction "O6_11") (pintype "open_collector"))
    )
    (net (code "106") (name "unconnected-(IC1-O7-Pad10)") (class "Default")
      (node (ref "IC1") (pin "10") (pinfunction "O7_10") (pintype "open_collector"))
    )
    (net (code "107") (name "unconnected-(R1-PadE)") (class "Default")
      (node (ref "R1") (pin "E") (pinfunction "E_E") (pintype "passive"))
    )
    (net (code "108") (name "unconnected-(R2-PadE)") (class "Default")
      (node (ref "R2") (pin "E") (pinfunction "E_E") (pintype "passive"))
    )
    (net (code "109") (name "unconnected-(R3-PadE)") (class "Default")
      (node (ref "R3") (pin "E") (pinfunction "E_E") (pintype "passive"))
    )
    (net (code "110") (name "unconnected-(S1-P1-Pad4)") (class "Default")
      (node (ref "S1") (pin "4") (pinfunction "P1_4") (pintype "passive"))
    )
    (net (code "111") (name "unconnected-(S1-S-Pad1)") (class "Default")
      (node (ref "S1") (pin "1") (pinfunction "S_1") (pintype "passive"))
    )
    (net (code "112") (name "unconnected-(S2-P1-Pad4)") (class "Default")
      (node (ref "S2") (pin "4") (pinfunction "P1_4") (pintype "passive"))
    )
    (net (code "113") (name "unconnected-(S2-S-Pad1)") (class "Default")
      (node (ref "S2") (pin "1") (pinfunction "S_1") (pintype "passive"))
    )
    (net (code "114") (name "unconnected-(S3-P1-Pad4)") (class "Default")
      (node (ref "S3") (pin "4") (pinfunction "P1_4") (pintype "passive"))
    )
    (net (code "115") (name "unconnected-(S3-S-Pad1)") (class "Default")
      (node (ref "S3") (pin "1") (pinfunction "S_1") (pintype "passive"))
    )
    (net (code "116") (name "unconnected-(S7-P-Pad3)") (class "Default")
      (node (ref "S7") (pin "3") (pinfunction "P_3") (pintype "passive"))
    )
    (net (code "117") (name "unconnected-(S7-S1-Pad2)") (class "Default")
      (node (ref "S7") (pin "2") (pinfunction "S1_2") (pintype "passive"))
    )
    (net (code "118") (name "unconnected-(U3-QE-Pad4)") (class "Default")
      (node (ref "U3") (pin "4") (pinfunction "QE_4") (pintype "tri_state"))
    )
    (net (code "119") (name "unconnected-(U3-QF-Pad5)") (class "Default")
      (node (ref "U3") (pin "5") (pinfunction "QF_5") (pintype "tri_state"))
    )
    (net (code "120") (name "unconnected-(U3-QG-Pad6)") (class "Default")
      (node (ref "U3") (pin "6") (pinfunction "QG_6") (pintype "tri_state"))
    )
    (net (code "121") (name "unconnected-(U3-QH*-Pad9)") (class "Default")
      (node (ref "U3") (pin "9") (pinfunction "QH*_9") (pintype "tri_state"))
    )
    (net (code "122") (name "unconnected-(U3-QH-Pad7)") (class "Default")
      (node (ref "U3") (pin "7") (pinfunction "QH_7") (pintype "tri_state"))
    )
    (net (code "123") (name "unconnected-(U4-QH*-Pad9)") (class "Default")
      (node (ref "U4") (pin "9") (pinfunction "QH*_9") (pintype "tri_state"))
    )
  )
)
